# schematic5.net
KiCad netlist of a schematic drawn in Altium Designer
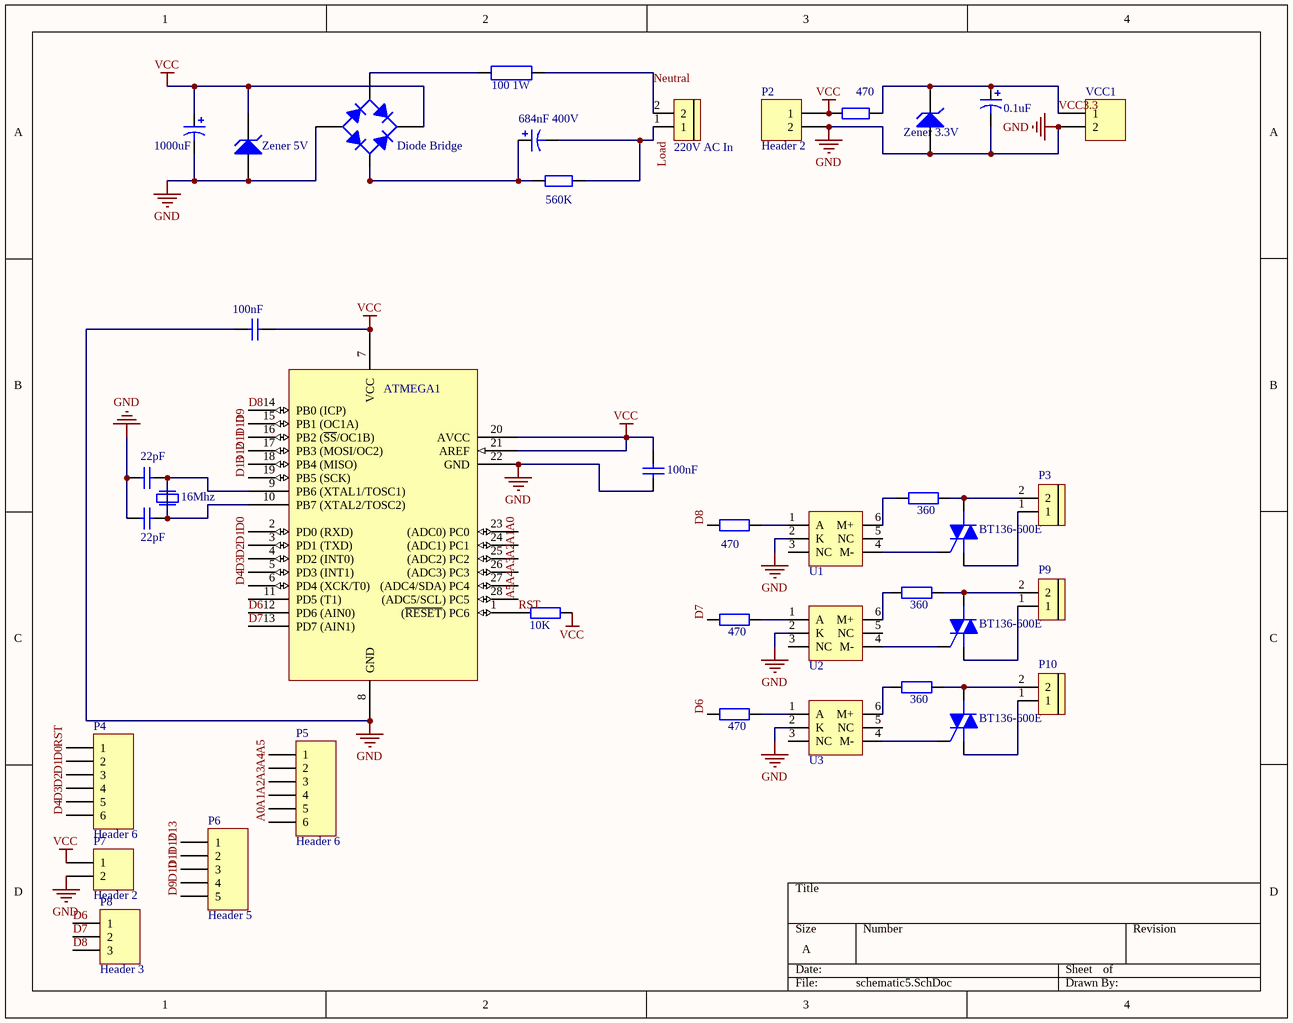
[diagram p0: schematic5.SchDoc]

(export (version "E")
  (design (tool "Eeschema 10.0.6"))
  (components
    (comp (ref "ATMEGA1")
      (value "ATMEGA8_DIP28")
      (footprint "DIP-28")
      (description "Atmel Microcontroller - Library created by carel..  <www.mpfreezone.com>")
      (libsource (lib "AVR") (part "ATMEGA8_DIP28"))
    )
    (comp (ref "C1")
      (value "0.1uF")
      (footprint "C3MM")
      (description "Polarized Capacitor (Axial)")
      (fields (field (name "PUBLISHER") "Altium Limited"))
      (libsource (lib "NBBLib 14-03-2012") (part "Cap Pol 3mm"))
    )
    (comp (ref "C2")
      (value "684nF 400V")
      (footprint "C10mm")
      (description "Polarized Capacitor (Axial)")
      (fields (field (name "PUBLISHER") "Altium Limited"))
      (libsource (lib "NBBLib 14-03-2012") (part "Cap Pol 12mm"))
    )
    (comp (ref "C3")
      (value "1000uF")
      (footprint "C10mm")
      (description "Polarized Capacitor (Axial)")
      (fields (field (name "PUBLISHER") "Altium Limited"))
      (libsource (lib "NBBLib 14-03-2012") (part "Cap Pol 8mm"))
    )
    (comp (ref "C4")
      (value "100nF")
      (footprint "Tu-pico")
      (description "Capacitor")
      (fields (field (name "PUBLISHER") "Altium Limited"))
      (libsource (lib "NBBLib 14-03-2012") (part "CapCeramic"))
    )
    (comp (ref "C5")
      (value "22pF")
      (footprint "Tu-pico")
      (description "Capacitor")
      (fields (field (name "PUBLISHER") "Altium Limited"))
      (libsource (lib "NBBLib 14-03-2012") (part "CapCeramic"))
    )
    (comp (ref "C6")
      (value "100nF")
      (footprint "Tu-pico")
      (description "Capacitor")
      (fields (field (name "PUBLISHER") "Altium Limited"))
      (libsource (lib "NBBLib 14-03-2012") (part "CapCeramic"))
    )
    (comp (ref "C7")
      (value "22pF")
      (footprint "Tu-pico")
      (description "Capacitor")
      (fields (field (name "PUBLISHER") "Altium Limited"))
      (libsource (lib "NBBLib 14-03-2012") (part "CapCeramic"))
    )
    (comp (ref "Crystal1") (value "16Mhz") (footprint "XTAL") (libsource (lib "tung k6") (part "XTAL")))
    (comp (ref "D1")
      (value "Diode Bridge")
      (footprint "D-38")
      (description "Full Wave Diode Bridge")
      (fields (field (name "PUBLISHER") "Altium Limited"))
      (libsource (lib "Miscellaneous Devices") (part "Bridge1"))
    )
    (comp (ref "D2")
      (value "Zener 3.3V")
      (footprint "DIODE/NOM/0.5A")
      (description "Zener Diode")
      (fields (field (name "PUBLISHER") "Altium Limited"))
      (libsource (lib "NBBLib 14-03-2012") (part "Diode Zener"))
    )
    (comp (ref "D3")
      (value "Zener 5V")
      (footprint "DIODE/NOM/0.5A")
      (description "Zener Diode")
      (fields (field (name "VOLTAGE") "5") (field (name "PUBLISHER") "Altium Limited"))
      (libsource (lib "NBBLib 14-03-2012") (part "Diode Zener"))
    )
    (comp (ref "P1")
      (value "220V AC In")
      (footprint "BIG_Header 2")
      (libsource (lib "NBBLib 14-03-2012") (part "BIG_Header 2"))
    )
    (comp (ref "P2")
      (value "Header 2")
      (footprint "HDR1X2")
      (description "Header, 2-Pin")
      (fields (field (name "PUBLISHER") "Altium Limited"))
      (libsource (lib "NBBLib 14-03-2012") (part "Header 2"))
    )
    (comp (ref "P3")
      (value "BIG_Header 2")
      (footprint "BIG_Header 2")
      (libsource (lib "NBBLib 14-03-2012") (part "BIG_Header 2"))
    )
    (comp (ref "P4")
      (value "Header 6")
      (footprint "HDR1X6")
      (description "Header, 6-Pin")
      (fields (field (name "PUBLISHER") "Altium Limited"))
      (libsource (lib "Miscellaneous Connectors") (part "Header 6"))
    )
    (comp (ref "P5")
      (value "Header 6")
      (footprint "HDR1X6")
      (description "Header, 6-Pin")
      (fields (field (name "PUBLISHER") "Altium Limited"))
      (libsource (lib "Miscellaneous Connectors") (part "Header 6"))
    )
    (comp (ref "P6")
      (value "Header 5")
      (footprint "HDR1X5")
      (description "Header, 5-Pin")
      (fields (field (name "PUBLISHER") "Altium Limited"))
      (libsource (lib "NBBLib 14-03-2012") (part "Header 5"))
    )
    (comp (ref "P7")
      (value "Header 2")
      (footprint "HDR1X2")
      (description "Header, 2-Pin")
      (fields (field (name "PUBLISHER") "Altium Limited"))
      (libsource (lib "Miscellaneous Connectors") (part "Header 2"))
    )
    (comp (ref "P8")
      (value "Header 3")
      (footprint "HDR1X3")
      (description "Header, 3-Pin")
      (fields (field (name "PUBLISHER") "Altium Limited"))
      (libsource (lib "NBBLib 14-03-2012") (part "Header 3"))
    )
    (comp (ref "P9")
      (value "BIG_Header 2")
      (footprint "BIG_Header 2")
      (libsource (lib "NBBLib 14-03-2012") (part "BIG_Header 2"))
    )
    (comp (ref "P10")
      (value "BIG_Header 2")
      (footprint "BIG_Header 2")
      (libsource (lib "NBBLib 14-03-2012") (part "BIG_Header 2"))
    )
    (comp (ref "Q1")
      (value "BT136-600E")
      (footprint "BTA6-600")
      (description "Silicon Bidirectional Triode Thyristor")
      (fields (field (name "PUBLISHER") "Altium Limited"))
      (libsource (lib "NBBLib 14-03-2012") (part "BTA12-600"))
    )
    (comp (ref "Q2")
      (value "BT136-600E")
      (footprint "BTA6-600")
      (description "Silicon Bidirectional Triode Thyristor")
      (fields (field (name "PUBLISHER") "Altium Limited"))
      (libsource (lib "NBBLib 14-03-2012") (part "BTA12-600"))
    )
    (comp (ref "Q3")
      (value "BT136-600E")
      (footprint "BTA6-600")
      (description "Silicon Bidirectional Triode Thyristor")
      (fields (field (name "PUBLISHER") "Altium Limited"))
      (libsource (lib "NBBLib 14-03-2012") (part "BTA12-600"))
    )
    (comp (ref "R1")
      (value "100 1W")
      (footprint "DIEN TRO 1W (tube)")
      (description "1W Res Power")
      (fields (field (name "VOLTAGE") "400") (field (name "CREATOR") "Nguyen Ba Bien"))
      (libsource (lib "NBBLib 14-03-2012") (part "Res 1W"))
    )
    (comp (ref "R2")
      (value "470")
      (footprint "DIEN TRO 1/4 W")
      (description "Resistor")
      (fields (field (name "Comment") "R0.4W") (field (name "PUBLISHER") "Altium Limited"))
      (libsource (lib "NBBLib 14-03-2012") (part "Res 1/4 W"))
    )
    (comp (ref "R3")
      (value "560K")
      (footprint "AXIAL-0.4")
      (description "Resistor")
      (fields (field (name "PUBLISHER") "Altium Limited"))
      (libsource (lib "Miscellaneous Devices") (part "Res2"))
    )
    (comp (ref "R4")
      (value "470")
      (footprint "R1/4W")
      (description "Resistor")
      (libsource (lib "t.thien") (part "R1/4W"))
    )
    (comp (ref "R5")
      (value "360")
      (footprint "R1/4W")
      (description "Resistor")
      (libsource (lib "t.thien") (part "R1/4W"))
    )
    (comp (ref "R6")
      (value "10K")
      (footprint "R1/4W")
      (description "Resistor")
      (libsource (lib "t.thien") (part "R1/4W"))
    )
    (comp (ref "R7")
      (value "470")
      (footprint "R1/4W")
      (description "Resistor")
      (libsource (lib "t.thien") (part "R1/4W"))
    )
    (comp (ref "R8")
      (value "360")
      (footprint "R1/4W")
      (description "Resistor")
      (libsource (lib "t.thien") (part "R1/4W"))
    )
    (comp (ref "R9")
      (value "470")
      (footprint "R1/4W")
      (description "Resistor")
      (libsource (lib "t.thien") (part "R1/4W"))
    )
    (comp (ref "R10")
      (value "360")
      (footprint "R1/4W")
      (description "Resistor")
      (libsource (lib "t.thien") (part "R1/4W"))
    )
    (comp (ref "U1")
      (value "MOC3021M")
      (footprint "MOC30XX")
      (libsource (lib "NBBLib 14-03-2012") (part "MOC3021M"))
    )
    (comp (ref "U2")
      (value "MOC3021M")
      (footprint "MOC30XX")
      (libsource (lib "NBBLib 14-03-2012") (part "MOC3021M"))
    )
    (comp (ref "U3")
      (value "MOC3021M")
      (footprint "MOC30XX")
      (libsource (lib "NBBLib 14-03-2012") (part "MOC3021M"))
    )
    (comp (ref "VCC1")
      (value "Header 2")
      (footprint "HDR1X2")
      (description "Header, 2-Pin")
      (fields (field (name "PUBLISHER") "Altium Limited"))
      (libsource (lib "") (part "Header 2_1"))
    )
  )
  (nets
    (net (code "1") (name "/A0") (class "Default")
      (node (ref "ATMEGA1") (pin "23") (pinfunction "(ADC0)_PC0_23") (pintype "bidirectional"))
      (node (ref "P5") (pin "6") (pinfunction "6_6") (pintype "passive"))
    )
    (net (code "2") (name "/A1") (class "Default")
      (node (ref "ATMEGA1") (pin "24") (pinfunction "(ADC1)_PC1_24") (pintype "bidirectional"))
      (node (ref "P5") (pin "5") (pinfunction "5_5") (pintype "passive"))
    )
    (net (code "3") (name "/A2") (class "Default")
      (node (ref "ATMEGA1") (pin "25") (pinfunction "(ADC2)_PC2_25") (pintype "bidirectional"))
      (node (ref "P5") (pin "4") (pinfunction "4_4") (pintype "passive"))
    )
    (net (code "4") (name "/A3") (class "Default")
      (node (ref "ATMEGA1") (pin "26") (pinfunction "(ADC3)_PC3_26") (pintype "bidirectional"))
      (node (ref "P5") (pin "3") (pinfunction "3_3") (pintype "passive"))
    )
    (net (code "5") (name "/A4") (class "Default")
      (node (ref "ATMEGA1") (pin "27") (pinfunction "(ADC4/SDA)_PC4_27") (pintype "bidirectional"))
      (node (ref "P5") (pin "2") (pinfunction "2_2") (pintype "passive"))
    )
    (net (code "6") (name "/A5") (class "Default")
      (node (ref "ATMEGA1") (pin "28") (pinfunction "(ADC5/SCL)_PC5_28") (pintype "bidirectional"))
      (node (ref "P5") (pin "1") (pinfunction "1_1") (pintype "passive"))
    )
    (net (code "7") (name "/D0") (class "Default")
      (node (ref "ATMEGA1") (pin "2") (pinfunction "PD0_(RXD)_2") (pintype "bidirectional"))
      (node (ref "P4") (pin "2") (pinfunction "2_2") (pintype "passive"))
    )
    (net (code "8") (name "/D1") (class "Default")
      (node (ref "ATMEGA1") (pin "3") (pinfunction "PD1_(TXD)_3") (pintype "bidirectional"))
      (node (ref "P4") (pin "3") (pinfunction "3_3") (pintype "passive"))
    )
    (net (code "9") (name "/D2") (class "Default")
      (node (ref "ATMEGA1") (pin "4") (pinfunction "PD2_(INT0)_4") (pintype "bidirectional"))
      (node (ref "P4") (pin "4") (pinfunction "4_4") (pintype "passive"))
    )
    (net (code "10") (name "/D3") (class "Default")
      (node (ref "ATMEGA1") (pin "5") (pinfunction "PD3_(INT1)_5") (pintype "bidirectional"))
      (node (ref "P4") (pin "5") (pinfunction "5_5") (pintype "passive"))
    )
    (net (code "11") (name "/D4") (class "Default")
      (node (ref "ATMEGA1") (pin "6") (pinfunction "PD4_(XCK/T0)_6") (pintype "bidirectional"))
      (node (ref "P4") (pin "6") (pinfunction "6_6") (pintype "passive"))
    )
    (net (code "12") (name "/D6") (class "Default")
      (node (ref "ATMEGA1") (pin "12") (pinfunction "PD6_(AIN0)_12") (pintype "passive"))
      (node (ref "P8") (pin "1") (pinfunction "1_1") (pintype "passive"))
      (node (ref "R9") (pin "1") (pinfunction "1_1") (pintype "passive"))
    )
    (net (code "13") (name "/D7") (class "Default")
      (node (ref "ATMEGA1") (pin "13") (pinfunction "PD7_(AIN1)_13") (pintype "passive"))
      (node (ref "P8") (pin "2") (pinfunction "2_2") (pintype "passive"))
      (node (ref "R7") (pin "1") (pinfunction "1_1") (pintype "passive"))
    )
    (net (code "14") (name "/D8") (class "Default")
      (node (ref "ATMEGA1") (pin "14") (pinfunction "PB0_(ICP)_14") (pintype "bidirectional"))
      (node (ref "P8") (pin "3") (pinfunction "3_3") (pintype "passive"))
      (node (ref "R4") (pin "1") (pinfunction "1_1") (pintype "passive"))
    )
    (net (code "15") (name "/D9") (class "Default")
      (node (ref "ATMEGA1") (pin "15") (pinfunction "PB1_(OC1A)_15") (pintype "bidirectional"))
      (node (ref "P6") (pin "5") (pinfunction "5_5") (pintype "passive"))
    )
    (net (code "16") (name "/D10") (class "Default")
      (node (ref "ATMEGA1") (pin "16") (pinfunction "PB2_(~{SS}/OC1B)_16") (pintype "bidirectional"))
      (node (ref "P6") (pin "4") (pinfunction "4_4") (pintype "passive"))
    )
    (net (code "17") (name "/D11") (class "Default")
      (node (ref "ATMEGA1") (pin "17") (pinfunction "PB3_(MOSI/OC2)_17") (pintype "bidirectional"))
      (node (ref "P6") (pin "3") (pinfunction "3_3") (pintype "passive"))
    )
    (net (code "18") (name "/D12") (class "Default")
      (node (ref "ATMEGA1") (pin "18") (pinfunction "PB4_(MISO)_18") (pintype "bidirectional"))
      (node (ref "P6") (pin "2") (pinfunction "2_2") (pintype "passive"))
    )
    (net (code "19") (name "/D13") (class "Default")
      (node (ref "ATMEGA1") (pin "19") (pinfunction "PB5_(SCK)_19") (pintype "bidirectional"))
      (node (ref "P6") (pin "1") (pinfunction "1_1") (pintype "passive"))
    )
    (net (code "20") (name "/Load") (class "Default")
      (node (ref "C2") (pin "2") (pinfunction "2_2") (pintype "passive"))
      (node (ref "P1") (pin "1") (pinfunction "1_1") (pintype "passive"))
      (node (ref "R3") (pin "2") (pinfunction "2_2") (pintype "passive"))
    )
    (net (code "21") (name "/Neutral") (class "Default")
      (node (ref "P1") (pin "2") (pinfunction "2_2") (pintype "passive"))
      (node (ref "R1") (pin "2") (pinfunction "2_2") (pintype "passive"))
    )
    (net (code "22") (name "/RST") (class "Default")
      (node (ref "ATMEGA1") (pin "1") (pinfunction "(~{RESET})_PC6_1") (pintype "bidirectional"))
      (node (ref "P4") (pin "1") (pinfunction "1_1") (pintype "passive"))
      (node (ref "R6") (pin "2") (pinfunction "2_2") (pintype "passive"))
    )
    (net (code "23") (name "/VCC3.3") (class "Default")
      (node (ref "C1") (pin "1") (pinfunction "1_1") (pintype "passive"))
      (node (ref "D2") (pin "2") (pinfunction "K_2") (pintype "passive"))
      (node (ref "R2") (pin "2") (pinfunction "2_2") (pintype "passive"))
      (node (ref "VCC1") (pin "1") (pinfunction "1_1") (pintype "passive"))
    )
    (net (code "24") (name "GND") (class "Default")
      (node (ref "ATMEGA1") (pin "22") (pinfunction "GND_22") (pintype "passive"))
      (node (ref "ATMEGA1") (pin "8") (pinfunction "GND_8") (pintype "passive"))
      (node (ref "C1") (pin "2") (pinfunction "2_2") (pintype "passive"))
      (node (ref "C3") (pin "2") (pinfunction "2_2") (pintype "passive"))
      (node (ref "C4") (pin "1") (pinfunction "1_1") (pintype "passive"))
      (node (ref "C5") (pin "2") (pinfunction "2_2") (pintype "passive"))
      (node (ref "C6") (pin "1") (pinfunction "1_1") (pintype "passive"))
      (node (ref "C7") (pin "2") (pinfunction "2_2") (pintype "passive"))
      (node (ref "D1") (pin "3") (pinfunction "A_3") (pintype "passive"))
      (node (ref "D2") (pin "1") (pinfunction "A_1") (pintype "passive"))
      (node (ref "D3") (pin "1") (pinfunction "A_1") (pintype "passive"))
      (node (ref "P2") (pin "2") (pinfunction "2_2") (pintype "passive"))
      (node (ref "P7") (pin "2") (pinfunction "2_2") (pintype "passive"))
      (node (ref "U1") (pin "2") (pinfunction "K_2") (pintype "passive"))
      (node (ref "U2") (pin "2") (pinfunction "K_2") (pintype "passive"))
      (node (ref "U3") (pin "2") (pinfunction "K_2") (pintype "passive"))
      (node (ref "VCC1") (pin "2") (pinfunction "2_2") (pintype "passive"))
    )
    (net (code "25") (name "Net-(ATMEGA1-PB6_(XTAL1{slash}TOSC1))") (class "Default")
      (node (ref "ATMEGA1") (pin "10") (pinfunction "PB7_(XTAL2/TOSC2)_10") (pintype "passive"))
      (node (ref "ATMEGA1") (pin "9") (pinfunction "PB6_(XTAL1/TOSC1)_9") (pintype "passive"))
      (node (ref "C5") (pin "1") (pinfunction "1_1") (pintype "passive"))
      (node (ref "C7") (pin "1") (pinfunction "1_1") (pintype "passive"))
      (node (ref "Crystal1") (pin "1") (pinfunction "P1_1") (pintype "passive"))
      (node (ref "Crystal1") (pin "2") (pinfunction "P2_2") (pintype "passive"))
    )
    (net (code "26") (name "Net-(C2-Pad1)") (class "Default")
      (node (ref "C2") (pin "1") (pinfunction "1_1") (pintype "passive"))
      (node (ref "D1") (pin "2") (pinfunction "C_2") (pintype "passive"))
      (node (ref "R3") (pin "1") (pinfunction "1_1") (pintype "passive"))
    )
    (net (code "27") (name "Net-(D1-C-Pad4)") (class "Default")
      (node (ref "D1") (pin "4") (pinfunction "C_4") (pintype "passive"))
      (node (ref "R1") (pin "1") (pinfunction "1_1") (pintype "passive"))
    )
    (net (code "28") (name "Net-(Q1-G)") (class "Default")
      (node (ref "Q1") (pin "3") (pinfunction "G_3") (pintype "passive"))
      (node (ref "U1") (pin "4") (pinfunction "M-_4") (pintype "passive"))
    )
    (net (code "29") (name "Net-(Q1-M1)") (class "Default")
      (node (ref "P3") (pin "1") (pinfunction "1_1") (pintype "passive"))
      (node (ref "Q1") (pin "1") (pinfunction "M1_1") (pintype "passive"))
    )
    (net (code "30") (name "Net-(Q1-M2)") (class "Default")
      (node (ref "P3") (pin "2") (pinfunction "2_2") (pintype "passive"))
      (node (ref "Q1") (pin "2") (pinfunction "M2_2") (pintype "passive"))
      (node (ref "R5") (pin "2") (pinfunction "2_2") (pintype "passive"))
    )
    (net (code "31") (name "Net-(Q2-G)") (class "Default")
      (node (ref "Q2") (pin "3") (pinfunction "G_3") (pintype "passive"))
      (node (ref "U2") (pin "4") (pinfunction "M-_4") (pintype "passive"))
    )
    (net (code "32") (name "Net-(Q2-M1)") (class "Default")
      (node (ref "P9") (pin "1") (pinfunction "1_1") (pintype "passive"))
      (node (ref "Q2") (pin "1") (pinfunction "M1_1") (pintype "passive"))
    )
    (net (code "33") (name "Net-(Q2-M2)") (class "Default")
      (node (ref "P9") (pin "2") (pinfunction "2_2") (pintype "passive"))
      (node (ref "Q2") (pin "2") (pinfunction "M2_2") (pintype "passive"))
      (node (ref "R8") (pin "2") (pinfunction "2_2") (pintype "passive"))
    )
    (net (code "34") (name "Net-(Q3-G)") (class "Default")
      (node (ref "Q3") (pin "3") (pinfunction "G_3") (pintype "passive"))
      (node (ref "U3") (pin "4") (pinfunction "M-_4") (pintype "passive"))
    )
    (net (code "35") (name "Net-(Q3-M1)") (class "Default")
      (node (ref "P10") (pin "1") (pinfunction "1_1") (pintype "passive"))
      (node (ref "Q3") (pin "1") (pinfunction "M1_1") (pintype "passive"))
    )
    (net (code "36") (name "Net-(Q3-M2)") (class "Default")
      (node (ref "P10") (pin "2") (pinfunction "2_2") (pintype "passive"))
      (node (ref "Q3") (pin "2") (pinfunction "M2_2") (pintype "passive"))
      (node (ref "R10") (pin "2") (pinfunction "2_2") (pintype "passive"))
    )
    (net (code "37") (name "Net-(U1-A)") (class "Default")
      (node (ref "R4") (pin "2") (pinfunction "2_2") (pintype "passive"))
      (node (ref "U1") (pin "1") (pinfunction "A_1") (pintype "passive"))
    )
    (net (code "38") (name "Net-(U1-M+)") (class "Default")
      (node (ref "R5") (pin "1") (pinfunction "1_1") (pintype "passive"))
      (node (ref "U1") (pin "6") (pinfunction "M+_6") (pintype "passive"))
    )
    (net (code "39") (name "Net-(U2-A)") (class "Default")
      (node (ref "R7") (pin "2") (pinfunction "2_2") (pintype "passive"))
      (node (ref "U2") (pin "1") (pinfunction "A_1") (pintype "passive"))
    )
    (net (code "40") (name "Net-(U2-M+)") (class "Default")
      (node (ref "R8") (pin "1") (pinfunction "1_1") (pintype "passive"))
      (node (ref "U2") (pin "6") (pinfunction "M+_6") (pintype "passive"))
    )
    (net (code "41") (name "Net-(U3-A)") (class "Default")
      (node (ref "R9") (pin "2") (pinfunction "2_2") (pintype "passive"))
      (node (ref "U3") (pin "1") (pinfunction "A_1") (pintype "passive"))
    )
    (net (code "42") (name "Net-(U3-M+)") (class "Default")
      (node (ref "R10") (pin "1") (pinfunction "1_1") (pintype "passive"))
      (node (ref "U3") (pin "6") (pinfunction "M+_6") (pintype "passive"))
    )
    (net (code "43") (name "VCC") (class "Default")
      (node (ref "ATMEGA1") (pin "20") (pinfunction "AVCC_20") (pintype "passive"))
      (node (ref "ATMEGA1") (pin "21") (pinfunction "AREF_21") (pintype "input"))
      (node (ref "ATMEGA1") (pin "7") (pinfunction "VCC_7") (pintype "passive"))
      (node (ref "C3") (pin "1") (pinfunction "1_1") (pintype "passive"))
      (node (ref "C4") (pin "2") (pinfunction "2_2") (pintype "passive"))
      (node (ref "C6") (pin "2") (pinfunction "2_2") (pintype "passive"))
      (node (ref "D1") (pin "1") (pinfunction "K_1") (pintype "passive"))
      (node (ref "D3") (pin "2") (pinfunction "K_2") (pintype "passive"))
      (node (ref "P2") (pin "1") (pinfunction "1_1") (pintype "passive"))
      (node (ref "P7") (pin "1") (pinfunction "1_1") (pintype "passive"))
      (node (ref "R2") (pin "1") (pinfunction "1_1") (pintype "passive"))
      (node (ref "R6") (pin "1") (pinfunction "1_1") (pintype "passive"))
    )
    (net (code "44") (name "unconnected-(ATMEGA1-PD5_(T1)-Pad11)") (class "Default")
      (node (ref "ATMEGA1") (pin "11") (pinfunction "PD5_(T1)_11") (pintype "passive"))
    )
    (net (code "45") (name "unconnected-(U1-NC-Pad3)") (class "Default")
      (node (ref "U1") (pin "3") (pinfunction "NC_3") (pintype "passive"))
    )
    (net (code "46") (name "unconnected-(U1-NC-Pad5)") (class "Default")
      (node (ref "U1") (pin "5") (pinfunction "NC_5") (pintype "passive"))
    )
    (net (code "47") (name "unconnected-(U2-NC-Pad3)") (class "Default")
      (node (ref "U2") (pin "3") (pinfunction "NC_3") (pintype "passive"))
    )
    (net (code "48") (name "unconnected-(U2-NC-Pad5)") (class "Default")
      (node (ref "U2") (pin "5") (pinfunction "NC_5") (pintype "passive"))
    )
    (net (code "49") (name "unconnected-(U3-NC-Pad3)") (class "Default")
      (node (ref "U3") (pin "3") (pinfunction "NC_3") (pintype "passive"))
    )
    (net (code "50") (name "unconnected-(U3-NC-Pad5)") (class "Default")
      (node (ref "U3") (pin "5") (pinfunction "NC_5") (pintype "passive"))
    )
  )
)
